# karmanDB_sensors2.net
KiCad netlist of a schematic drawn in Altium Designer
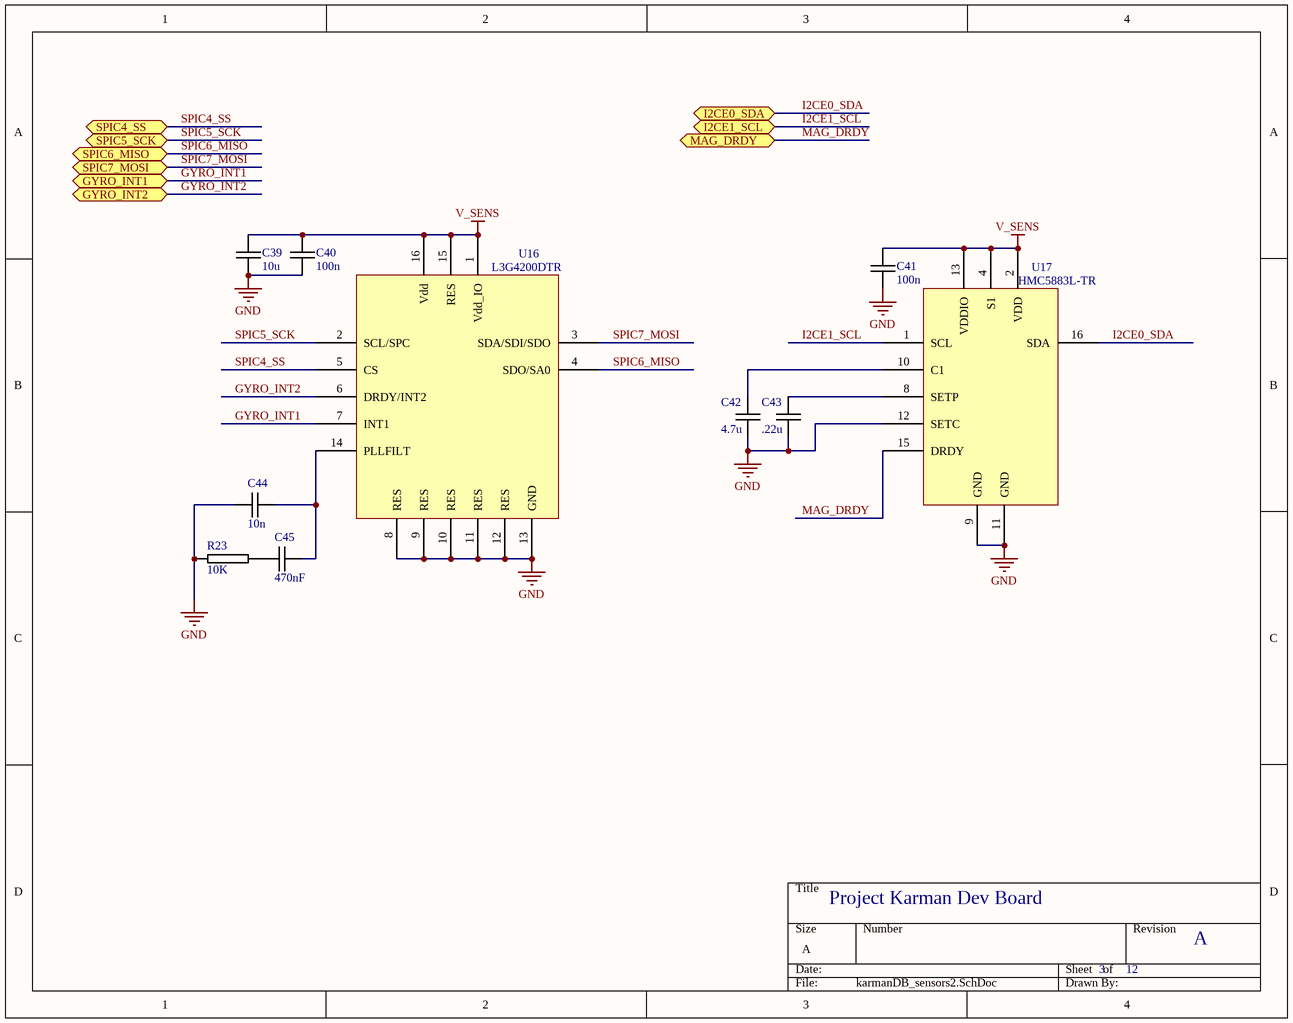
[diagram p0: karmanDB_sensors2.SchDoc]

(export (version "E")
  (design (tool "Eeschema 10.0.6"))
  (components
    (comp (ref "C39")
      (value "10u")
      (footprint "MURATA_GRM_0603")
      (description "CAP CER 10UF 6.3V 20% X5R 0603")
      (fields
        (field (name "MANUFACTURER") "Murata Electronics North America")
        (field (name "MANUFACTURER PART NUMBER") "GRM188R60J106ME47J")
      )
      (libsource (lib "project_symbols") (part "CAP_MURATA_GRM188R60J106"))
    )
    (comp (ref "C40")
      (value "100n")
      (footprint "MURATA_GRM_0603")
      (description "CAP CER 0.1UF 6.3V 10% X7R 0603")
      (fields
        (field (name "MANUFACTURER") "Murata Electronics North America")
        (field (name "MANUFACTURER PART NUMBER") "GRM188R70J104KA01D")
      )
      (libsource (lib "project_symbols") (part "CAP_MURATA_GRM188R70J104KA01D"))
    )
    (comp (ref "C41")
      (value "100n")
      (footprint "MURATA_GRM_0603")
      (description "CAP CER 0.1UF 16V 10% X7R 0603")
      (fields
        (field (name "MANUFACTURER") "Murata Electronics North America")
        (field (name "MANUFACTURER PART NUMBER") "GRM188R71C104KA01D")
      )
      (libsource (lib "project_symbols") (part "CAP_MURATA_GRM188R71C104KA01D"))
    )
    (comp (ref "C42")
      (value "4.7u")
      (footprint "MURATA_GRM_0603")
      (description "CAP CER 4.7UF 16V 20% X5R 0603")
      (fields
        (field (name "MANUFACTURER") "Murata Electronics North America")
        (field (name "MANUFACTURER PART NUMBER") "GRM188R61C475MAAJD")
      )
      (libsource (lib "project_symbols") (part "CAP_MURATA_GRM188R61C475MAAJD"))
    )
    (comp (ref "C43")
      (value ".22u")
      (footprint "MURATA_GRM_0603")
      (description "CAP CER 0.22UF 25V 10% X7R 0603")
      (fields
        (field (name "MANUFACTURER") "Murata Electronics North America")
        (field (name "MANUFACTURER PART NUMBER") "GRM188R71E224KA88D")
      )
      (libsource (lib "project_symbols") (part "CAP_MURATA_GRM188R71E224KA88D"))
    )
    (comp (ref "C44")
      (value "10n")
      (footprint "MURATA_GRM_0402")
      (description "CAP CER 10000PF 16V 10% X7R 0402")
      (fields
        (field (name "MANUFACTURER") "Murata Electronics North America")
        (field (name "MANUFACTURER PART NUMBER") "GRM155R71C103KA01D")
      )
      (libsource (lib "project_symbols") (part "CAP_MURATA_GRM155R71C103KA01D"))
    )
    (comp (ref "C45")
      (value "470nF")
      (footprint "project_footprints:MURATA_GRM_0402")
      (description "CAP CER 0.47UF 16V 10% X5R 0402")
      (fields
        (field (name "MANUFACTURER") "Murata Electronics North America")
        (field (name "MANUFACTURER PART NUMBER") "GRT155R61C474KE01D")
      )
      (libsource (lib "project_symbols") (part "CAP_MURATA_GRT155R61C474KE01D"))
    )
    (comp (ref "R23")
      (value "10K")
      (footprint "PANASONIC_ERJ3R")
      (description "RES SMD 10K OHM 5% 1/10W 0603")
      (fields
        (field (name "MANUFACTURER") "Panasonic Electronic Components")
        (field (name "MANUFACTURER PART NUMBER") "ERJ-3GEYJ103V")
      )
      (libsource (lib "project_symbols") (part "RES_PANASONIC_ERJ-3GEYJ103V"))
    )
    (comp (ref "U16")
      (value "L3G4200DTR")
      (footprint "4 L3G4200D")
      (description "IC GYROSCOPE MEMS 3AXIS LP 16LGA")
      (fields (field (name "MANUFACTURER") "STMicroelectronics"))
      (libsource (lib "karman_pcb") (part "L3G4200DTR"))
    )
    (comp (ref "U17")
      (value "HMC5883L-TR")
      (footprint "5 HMC5883L-TR")
      (description "IC COMPASS 3 AXIS I2C 16LCC SMD")
      (fields (field (name "MANUFACTURER") "Honeywell Microelectronics & Precision Sensors"))
      (libsource (lib "karman_pcb") (part "HMC5883L-TR"))
    )
  )
  (nets
    (net (code "1") (name "/GYRO_INT1") (class "Default")
      (node (ref "U16") (pin "7") (pinfunction "INT1_7") (pintype "passive"))
    )
    (net (code "2") (name "/GYRO_INT2") (class "Default")
      (node (ref "U16") (pin "6") (pinfunction "DRDY/INT2_6") (pintype "passive"))
    )
    (net (code "3") (name "/I2CE0_SDA") (class "Default")
      (node (ref "U17") (pin "16") (pinfunction "SDA_16") (pintype "passive"))
    )
    (net (code "4") (name "/I2CE1_SCL") (class "Default")
      (node (ref "U17") (pin "1") (pinfunction "SCL_1") (pintype "passive"))
    )
    (net (code "5") (name "/MAG_DRDY") (class "Default")
      (node (ref "U17") (pin "15") (pinfunction "DRDY_15") (pintype "passive"))
    )
    (net (code "6") (name "/SPIC4_SS") (class "Default")
      (node (ref "U16") (pin "5") (pinfunction "CS_5") (pintype "passive"))
    )
    (net (code "7") (name "/SPIC5_SCK") (class "Default")
      (node (ref "U16") (pin "2") (pinfunction "SCL/SPC_2") (pintype "passive"))
    )
    (net (code "8") (name "/SPIC6_MISO") (class "Default")
      (node (ref "U16") (pin "4") (pinfunction "SDO/SA0_4") (pintype "passive"))
    )
    (net (code "9") (name "/SPIC7_MOSI") (class "Default")
      (node (ref "U16") (pin "3") (pinfunction "SDA/SDI/SDO_3") (pintype "passive"))
    )
    (net (code "10") (name "GND") (class "Default")
      (node (ref "C39") (pin "2") (pintype "passive"))
      (node (ref "C40") (pin "2") (pintype "passive"))
      (node (ref "C41") (pin "2") (pintype "passive"))
      (node (ref "C42") (pin "2") (pintype "passive"))
      (node (ref "C43") (pin "2") (pintype "passive"))
      (node (ref "C44") (pin "1") (pintype "passive"))
      (node (ref "R23") (pin "1") (pintype "passive"))
      (node (ref "U16") (pin "10") (pinfunction "RES_10") (pintype "passive"))
      (node (ref "U16") (pin "11") (pinfunction "RES_11") (pintype "passive"))
      (node (ref "U16") (pin "12") (pinfunction "RES_12") (pintype "passive"))
      (node (ref "U16") (pin "13") (pinfunction "GND_13") (pintype "passive"))
      (node (ref "U16") (pin "8") (pinfunction "RES_8") (pintype "passive"))
      (node (ref "U16") (pin "9") (pinfunction "RES_9") (pintype "passive"))
      (node (ref "U17") (pin "11") (pinfunction "GND_11") (pintype "passive"))
      (node (ref "U17") (pin "12") (pinfunction "SETC_12") (pintype "passive"))
      (node (ref "U17") (pin "9") (pinfunction "GND_9") (pintype "passive"))
    )
    (net (code "11") (name "Net-(C45-Pad1)") (class "Default")
      (node (ref "C45") (pin "1") (pintype "passive"))
      (node (ref "R23") (pin "2") (pintype "passive"))
    )
    (net (code "12") (name "Net-(U16-PLLFILT)") (class "Default")
      (node (ref "C44") (pin "2") (pintype "passive"))
      (node (ref "C45") (pin "2") (pintype "passive"))
      (node (ref "U16") (pin "14") (pinfunction "PLLFILT_14") (pintype "passive"))
    )
    (net (code "13") (name "Net-(U17-C1)") (class "Default")
      (node (ref "C42") (pin "1") (pintype "passive"))
      (node (ref "U17") (pin "10") (pinfunction "C1_10") (pintype "passive"))
    )
    (net (code "14") (name "Net-(U17-SETP)") (class "Default")
      (node (ref "C43") (pin "1") (pintype "passive"))
      (node (ref "U17") (pin "8") (pinfunction "SETP_8") (pintype "passive"))
    )
    (net (code "15") (name "V_SENS") (class "Default")
      (node (ref "C39") (pin "1") (pintype "passive"))
      (node (ref "C40") (pin "1") (pintype "passive"))
      (node (ref "C41") (pin "1") (pintype "passive"))
      (node (ref "U16") (pin "1") (pinfunction "Vdd_IO_1") (pintype "passive"))
      (node (ref "U16") (pin "15") (pinfunction "RES_15") (pintype "passive"))
      (node (ref "U16") (pin "16") (pinfunction "Vdd_16") (pintype "passive"))
      (node (ref "U17") (pin "13") (pinfunction "VDDIO_13") (pintype "passive"))
      (node (ref "U17") (pin "2") (pinfunction "VDD_2") (pintype "passive"))
      (node (ref "U17") (pin "4") (pinfunction "S1_4") (pintype "passive"))
    )
  )
)
